# RPi.net
KiCad netlist of a schematic drawn in Altium Designer
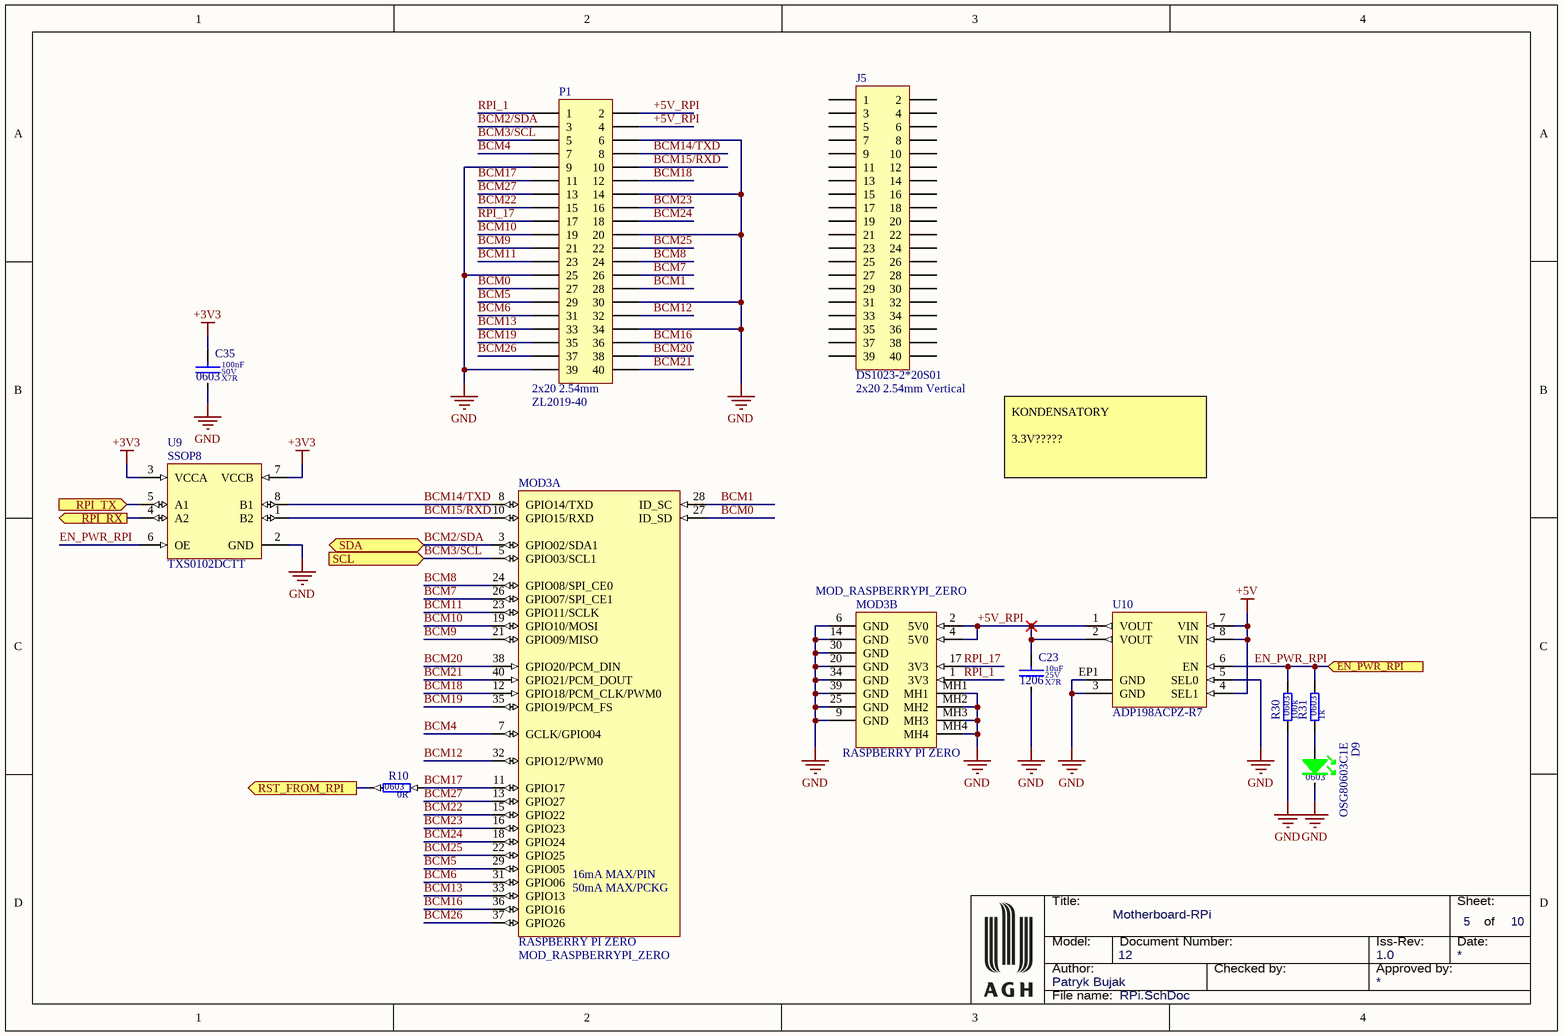
[diagram p0: RPi.SchDoc]

(export (version "E")
  (design (tool "Eeschema 10.0.6"))
  (components
    (comp (ref "C23")
      (value "10uF")
      (footprint "C_1206_3216")
      (description "Capacitor")
      (fields
        (field (name "DIELECTRIC") "X7R")
        (field (name "VOLTAGE") "25V")
        (field (name "SCH_FOOTPRINT") "1206")
        (field (name "PART NUMBER") "C_10uF_25V_X7R_1206_10")
        (field (name "MANUFACTURER") "Samsung Electro-Mechanics")
      )
      (libsource (lib "Library") (part "C"))
    )
    (comp (ref "C35")
      (value "100nF")
      (footprint "C_0603_1608")
      (description "Capacitor")
      (fields
        (field (name "DIELECTRIC") "X7R")
        (field (name "VOLTAGE") "50V")
        (field (name "SCH_FOOTPRINT") "0603")
        (field (name "PART NUMBER") "C_100nF_50V_X7R_0603_5")
        (field (name "MANUFACTURER") "Samsung")
      )
      (libsource (lib "Library") (part "C"))
    )
    (comp (ref "D9")
      (value "OSG80603C1E")
      (footprint "OL_0603_1608")
      (description "LED GREEN")
      (fields
        (field (name "SCH_FOOTPRINT") "0603")
        (field (name "PART NUMBER") "OL_G_0603_OSG80603C1E")
        (field (name "MANUFACTURER") "Optosupply")
      )
      (libsource (lib "Library") (part "OL_G"))
    )
    (comp (ref "J5")
      (value "DS1023-2*20S01")
      (footprint "J_HEADER_2x20_2.54_VERTICAL")
      (description "Header, 40-Pin, Dual row")
      (fields
        (field (name "PART NUMBER") "J_HEADER_2x20_2.54_VERTICAL")
        (field (name "SCH_FOOTPRINT") "2x20 2.54mm Vertical")
        (field (name "MANUFACTURER") "Connfly")
      )
      (libsource (lib "Library") (part "J_HEADER_2x20"))
    )
    (comp (ref "MOD3")
      (value "RASPBERRY PI ZERO")
      (footprint "MOD_RASPBERRYPI_ZERO")
      (fields
        (field (name "PART NUMBER") "MOD_RASPBERRYPI_ZERO")
        (field (name "SCH_FOOTPRINT") "MOD_RASPBERRYPI_ZERO")
        (field (name "MANUFACTURER") "Raspberry Pi")
      )
      (libsource (lib "Library") (part "MOD_RASPBERRYPI_3B"))
    )
    (comp (ref "P1")
      (value "ZL2019-40")
      (footprint "P_HEADER_2x20_2.54_HIGH")
      (description "Header, 19-Pin, Dual row")
      (fields
        (field (name "SCH_FOOTPRINT") "2x20 2.54mm")
        (field (name "PART NUMBER") "P_HEADER_2x20_2.54_HIGH")
        (field (name "MANUFACTURER") "Ninigi")
      )
      (libsource (lib "Library") (part "P_HEADER_2x20"))
    )
    (comp (ref "R10")
      (value "0R")
      (footprint "R_0603_1608")
      (fields
        (field (name "SCH_FOOTPRINT") "0603")
        (field (name "PART NUMBER") "R_0R_0603_5")
        (field (name "VOLTAGE") "50V")
        (field (name "POWER") "100mW")
      )
      (libsource (lib "") (part "R_1"))
    )
    (comp (ref "R30")
      (value "100k")
      (footprint "R_0603_1608")
      (fields
        (field (name "SCH_FOOTPRINT") "0603")
        (field (name "PART NUMBER") "R_100k_0603_1")
        (field (name "VOLTAGE") "50V")
        (field (name "POWER") "100mW")
      )
      (libsource (lib "Library") (part "R"))
    )
    (comp (ref "R31")
      (value "1k")
      (footprint "R_0603_1608")
      (fields
        (field (name "SCH_FOOTPRINT") "0603")
        (field (name "PART NUMBER") "R_1k_0603_1")
        (field (name "VOLTAGE") "75V")
        (field (name "POWER") "100mW")
      )
      (libsource (lib "Library") (part "R"))
    )
    (comp (ref "U9")
      (value "TXS0102DCTT")
      (footprint "SSOP8_3x3")
      (fields
        (field (name "SCH_FOOTPRINT") "SSOP8")
        (field (name "PART NUMBER") "U_TXS0102DCTT")
        (field (name "MANUFACTURER") "Texas Instruments")
      )
      (libsource (lib "Library") (part "U_TXS0102_DCT_DCU"))
    )
    (comp (ref "U10")
      (value "ADP198ACPZ-R7")
      (footprint "LFCSP-8-10")
      (fields
        (field (name "SCH_FOOTPRINT") "LFCSP8")
        (field (name "PART NUMBER") "U_ADP198ACPZ-R7")
        (field (name "MANUFACTURER") "Analog Devices")
        (field (name "Comment") "high-side load switch")
      )
      (libsource (lib "Library") (part "U_ADP198ACPZ-R7"))
    )
  )
  (nets
    (net (code "1") (name "+3V3") (class "Default")
      (node (ref "C35") (pin "1") (pinfunction "1_1") (pintype "passive"))
      (node (ref "U9") (pin "3") (pinfunction "VCCA_3") (pintype "input"))
      (node (ref "U9") (pin "7") (pinfunction "VCCB_7") (pintype "input"))
    )
    (net (code "2") (name "+5V") (class "Default")
      (node (ref "U10") (pin "4") (pinfunction "SEL1_4") (pintype "input"))
      (node (ref "U10") (pin "7") (pinfunction "VIN_7") (pintype "input"))
      (node (ref "U10") (pin "8") (pinfunction "VIN_8") (pintype "input"))
    )
    (net (code "3") (name "/+5V_RPI") (class "Default")
      (node (ref "C23") (pin "1") (pinfunction "1_1") (pintype "passive"))
      (node (ref "MOD3") (pin "2") (pinfunction "5V0_2") (pintype "input"))
      (node (ref "MOD3") (pin "4") (pinfunction "5V0_4") (pintype "input"))
      (node (ref "P1") (pin "2") (pinfunction "2_2") (pintype "passive"))
      (node (ref "P1") (pin "4") (pinfunction "4_4") (pintype "passive"))
      (node (ref "U10") (pin "1") (pinfunction "VOUT_1") (pintype "output"))
      (node (ref "U10") (pin "2") (pinfunction "VOUT_2") (pintype "output"))
    )
    (net (code "4") (name "/BCM0") (class "Default")
      (node (ref "MOD3") (pin "27") (pinfunction "ID_SD_27") (pintype "input"))
      (node (ref "P1") (pin "27") (pinfunction "27_27") (pintype "passive"))
    )
    (net (code "5") (name "/BCM1") (class "Default")
      (node (ref "MOD3") (pin "28") (pinfunction "ID_SC_28") (pintype "input"))
      (node (ref "P1") (pin "28") (pinfunction "28_28") (pintype "passive"))
    )
    (net (code "6") (name "/BCM2{slash}SDA") (class "Default")
      (node (ref "MOD3") (pin "3") (pinfunction "GPIO02/SDA1_3") (pintype "bidirectional"))
      (node (ref "P1") (pin "3") (pinfunction "3_3") (pintype "passive"))
    )
    (net (code "7") (name "/BCM3{slash}SCL") (class "Default")
      (node (ref "MOD3") (pin "5") (pinfunction "GPIO03/SCL1_5") (pintype "bidirectional"))
      (node (ref "P1") (pin "5") (pinfunction "5_5") (pintype "passive"))
    )
    (net (code "8") (name "/BCM4") (class "Default")
      (node (ref "MOD3") (pin "7") (pinfunction "GCLK/GPIO04_7") (pintype "bidirectional"))
      (node (ref "P1") (pin "7") (pinfunction "7_7") (pintype "passive"))
    )
    (net (code "9") (name "/BCM5") (class "Default")
      (node (ref "MOD3") (pin "29") (pinfunction "GPIO05_29") (pintype "bidirectional"))
      (node (ref "P1") (pin "29") (pinfunction "29_29") (pintype "passive"))
    )
    (net (code "10") (name "/BCM6") (class "Default")
      (node (ref "MOD3") (pin "31") (pinfunction "GPIO06_31") (pintype "bidirectional"))
      (node (ref "P1") (pin "31") (pinfunction "31_31") (pintype "passive"))
    )
    (net (code "11") (name "/BCM7") (class "Default")
      (node (ref "MOD3") (pin "26") (pinfunction "GPIO07/SPI_CE1_26") (pintype "bidirectional"))
      (node (ref "P1") (pin "26") (pinfunction "26_26") (pintype "passive"))
    )
    (net (code "12") (name "/BCM8") (class "Default")
      (node (ref "MOD3") (pin "24") (pinfunction "GPIO08/SPI_CE0_24") (pintype "bidirectional"))
      (node (ref "P1") (pin "24") (pinfunction "24_24") (pintype "passive"))
    )
    (net (code "13") (name "/BCM9") (class "Default")
      (node (ref "MOD3") (pin "21") (pinfunction "GPIO09/MISO_21") (pintype "bidirectional"))
      (node (ref "P1") (pin "21") (pinfunction "21_21") (pintype "passive"))
    )
    (net (code "14") (name "/BCM10") (class "Default")
      (node (ref "MOD3") (pin "19") (pinfunction "GPIO10/MOSI_19") (pintype "bidirectional"))
      (node (ref "P1") (pin "19") (pinfunction "19_19") (pintype "passive"))
    )
    (net (code "15") (name "/BCM11") (class "Default")
      (node (ref "MOD3") (pin "23") (pinfunction "GPIO11/SCLK_23") (pintype "bidirectional"))
      (node (ref "P1") (pin "23") (pinfunction "23_23") (pintype "passive"))
    )
    (net (code "16") (name "/BCM12") (class "Default")
      (node (ref "MOD3") (pin "32") (pinfunction "GPIO12/PWM0_32") (pintype "bidirectional"))
      (node (ref "P1") (pin "32") (pinfunction "32_32") (pintype "passive"))
    )
    (net (code "17") (name "/BCM13") (class "Default")
      (node (ref "MOD3") (pin "33") (pinfunction "GPIO13_33") (pintype "bidirectional"))
      (node (ref "P1") (pin "33") (pinfunction "33_33") (pintype "passive"))
    )
    (net (code "18") (name "/BCM14{slash}TXD") (class "Default")
      (node (ref "MOD3") (pin "8") (pinfunction "GPIO14/TXD_8") (pintype "bidirectional"))
      (node (ref "P1") (pin "8") (pinfunction "8_8") (pintype "passive"))
      (node (ref "U9") (pin "8") (pinfunction "B1_8") (pintype "bidirectional"))
    )
    (net (code "19") (name "/BCM15{slash}RXD") (class "Default")
      (node (ref "MOD3") (pin "10") (pinfunction "GPIO15/RXD_10") (pintype "bidirectional"))
      (node (ref "P1") (pin "10") (pinfunction "10_10") (pintype "passive"))
      (node (ref "U9") (pin "1") (pinfunction "B2_1") (pintype "bidirectional"))
    )
    (net (code "20") (name "/BCM16") (class "Default")
      (node (ref "MOD3") (pin "36") (pinfunction "GPIO16_36") (pintype "bidirectional"))
      (node (ref "P1") (pin "36") (pinfunction "36_36") (pintype "passive"))
    )
    (net (code "21") (name "/BCM17") (class "Default")
      (node (ref "MOD3") (pin "11") (pinfunction "GPIO17_11") (pintype "bidirectional"))
      (node (ref "P1") (pin "11") (pinfunction "11_11") (pintype "passive"))
      (node (ref "R10") (pin "1") (pinfunction "1_1") (pintype "input"))
    )
    (net (code "22") (name "/BCM18") (class "Default")
      (node (ref "MOD3") (pin "12") (pinfunction "GPIO18/PCM_CLK/PWM0_12") (pintype "input"))
      (node (ref "P1") (pin "12") (pinfunction "12_12") (pintype "passive"))
    )
    (net (code "23") (name "/BCM19") (class "Default")
      (node (ref "MOD3") (pin "35") (pinfunction "GPIO19/PCM_FS_35") (pintype "bidirectional"))
      (node (ref "P1") (pin "35") (pinfunction "35_35") (pintype "passive"))
    )
    (net (code "24") (name "/BCM20") (class "Default")
      (node (ref "MOD3") (pin "38") (pinfunction "GPIO20/PCM_DIN_38") (pintype "input"))
      (node (ref "P1") (pin "38") (pinfunction "38_38") (pintype "passive"))
    )
    (net (code "25") (name "/BCM21") (class "Default")
      (node (ref "MOD3") (pin "40") (pinfunction "GPIO21/PCM_DOUT_40") (pintype "input"))
      (node (ref "P1") (pin "40") (pinfunction "40_40") (pintype "passive"))
    )
    (net (code "26") (name "/BCM22") (class "Default")
      (node (ref "MOD3") (pin "15") (pinfunction "GPIO22_15") (pintype "bidirectional"))
      (node (ref "P1") (pin "15") (pinfunction "15_15") (pintype "passive"))
    )
    (net (code "27") (name "/BCM23") (class "Default")
      (node (ref "MOD3") (pin "16") (pinfunction "GPIO23_16") (pintype "bidirectional"))
      (node (ref "P1") (pin "16") (pinfunction "16_16") (pintype "passive"))
    )
    (net (code "28") (name "/BCM24") (class "Default")
      (node (ref "MOD3") (pin "18") (pinfunction "GPIO24_18") (pintype "bidirectional"))
      (node (ref "P1") (pin "18") (pinfunction "18_18") (pintype "passive"))
    )
    (net (code "29") (name "/BCM25") (class "Default")
      (node (ref "MOD3") (pin "22") (pinfunction "GPIO25_22") (pintype "bidirectional"))
      (node (ref "P1") (pin "22") (pinfunction "22_22") (pintype "passive"))
    )
    (net (code "30") (name "/BCM26") (class "Default")
      (node (ref "MOD3") (pin "37") (pinfunction "GPIO26_37") (pintype "bidirectional"))
      (node (ref "P1") (pin "37") (pinfunction "37_37") (pintype "passive"))
    )
    (net (code "31") (name "/BCM27") (class "Default")
      (node (ref "MOD3") (pin "13") (pinfunction "GPIO27_13") (pintype "bidirectional"))
      (node (ref "P1") (pin "13") (pinfunction "13_13") (pintype "passive"))
    )
    (net (code "32") (name "/EN_PWR_RPI") (class "Default")
      (node (ref "R30") (pin "2") (pinfunction "2_2") (pintype "passive"))
      (node (ref "R31") (pin "2") (pinfunction "2_2") (pintype "passive"))
      (node (ref "U10") (pin "6") (pinfunction "EN_6") (pintype "input"))
      (node (ref "U9") (pin "6") (pinfunction "OE_6") (pintype "input"))
    )
    (net (code "33") (name "/RPI_1") (class "Default")
      (node (ref "MOD3") (pin "1") (pinfunction "3V3_1") (pintype "input"))
      (node (ref "P1") (pin "1") (pinfunction "1_1") (pintype "passive"))
    )
    (net (code "34") (name "/RPI_17") (class "Default")
      (node (ref "MOD3") (pin "17") (pinfunction "3V3_17") (pintype "input"))
      (node (ref "P1") (pin "17") (pinfunction "17_17") (pintype "passive"))
    )
    (net (code "35") (name "/RPI_RX") (class "Default")
      (node (ref "U9") (pin "4") (pinfunction "A2_4") (pintype "bidirectional"))
    )
    (net (code "36") (name "/RPI_TX") (class "Default")
      (node (ref "U9") (pin "5") (pinfunction "A1_5") (pintype "bidirectional"))
    )
    (net (code "37") (name "/RST_FROM_RPI") (class "Default")
      (node (ref "R10") (pin "2") (pinfunction "2_2") (pintype "output"))
    )
    (net (code "38") (name "GND") (class "Default")
      (node (ref "C23") (pin "2") (pinfunction "2_2") (pintype "passive"))
      (node (ref "C35") (pin "2") (pinfunction "2_2") (pintype "passive"))
      (node (ref "D9") (pin "1") (pinfunction "K_1") (pintype "passive"))
      (node (ref "MOD3") (pin "14") (pinfunction "GND_14") (pintype "power_in"))
      (node (ref "MOD3") (pin "20") (pinfunction "GND_20") (pintype "power_in"))
      (node (ref "MOD3") (pin "25") (pinfunction "GND_25") (pintype "power_in"))
      (node (ref "MOD3") (pin "30") (pinfunction "GND_30") (pintype "power_in"))
      (node (ref "MOD3") (pin "34") (pinfunction "GND_34") (pintype "power_in"))
      (node (ref "MOD3") (pin "39") (pinfunction "GND_39") (pintype "power_in"))
      (node (ref "MOD3") (pin "6") (pinfunction "GND_6") (pintype "power_in"))
      (node (ref "MOD3") (pin "9") (pinfunction "GND_9") (pintype "power_in"))
      (node (ref "MOD3") (pin "MH1") (pinfunction "MH1_MH1") (pintype "passive"))
      (node (ref "MOD3") (pin "MH2") (pinfunction "MH2_MH2") (pintype "passive"))
      (node (ref "MOD3") (pin "MH3") (pinfunction "MH3_MH3") (pintype "passive"))
      (node (ref "MOD3") (pin "MH4") (pinfunction "MH4_MH4") (pintype "passive"))
      (node (ref "P1") (pin "14") (pinfunction "14_14") (pintype "passive"))
      (node (ref "P1") (pin "20") (pinfunction "20_20") (pintype "passive"))
      (node (ref "P1") (pin "25") (pinfunction "25_25") (pintype "passive"))
      (node (ref "P1") (pin "30") (pinfunction "30_30") (pintype "passive"))
      (node (ref "P1") (pin "34") (pinfunction "34_34") (pintype "passive"))
      (node (ref "P1") (pin "39") (pinfunction "39_39") (pintype "passive"))
      (node (ref "P1") (pin "6") (pinfunction "6_6") (pintype "passive"))
      (node (ref "P1") (pin "9") (pinfunction "9_9") (pintype "passive"))
      (node (ref "R30") (pin "1") (pinfunction "1_1") (pintype "passive"))
      (node (ref "U10") (pin "3") (pinfunction "GND_3") (pintype "power_in"))
      (node (ref "U10") (pin "5") (pinfunction "SEL0_5") (pintype "input"))
      (node (ref "U10") (pin "EP1") (pinfunction "GND_EP1") (pintype "power_in"))
      (node (ref "U9") (pin "2") (pinfunction "GND_2") (pintype "power_in"))
    )
    (net (code "39") (name "Net-(D9-A)") (class "Default")
      (node (ref "D9") (pin "2") (pinfunction "A_2") (pintype "passive"))
      (node (ref "R31") (pin "1") (pinfunction "1_1") (pintype "passive"))
    )
    (net (code "40") (name "unconnected-(J5-Pad1)") (class "Default")
      (node (ref "J5") (pin "1") (pinfunction "1_1") (pintype "passive"))
    )
    (net (code "41") (name "unconnected-(J5-Pad2)") (class "Default")
      (node (ref "J5") (pin "2") (pinfunction "2_2") (pintype "passive"))
    )
    (net (code "42") (name "unconnected-(J5-Pad3)") (class "Default")
      (node (ref "J5") (pin "3") (pinfunction "3_3") (pintype "passive"))
    )
    (net (code "43") (name "unconnected-(J5-Pad4)") (class "Default")
      (node (ref "J5") (pin "4") (pinfunction "4_4") (pintype "passive"))
    )
    (net (code "44") (name "unconnected-(J5-Pad5)") (class "Default")
      (node (ref "J5") (pin "5") (pinfunction "5_5") (pintype "passive"))
    )
    (net (code "45") (name "unconnected-(J5-Pad6)") (class "Default")
      (node (ref "J5") (pin "6") (pinfunction "6_6") (pintype "passive"))
    )
    (net (code "46") (name "unconnected-(J5-Pad7)") (class "Default")
      (node (ref "J5") (pin "7") (pinfunction "7_7") (pintype "passive"))
    )
    (net (code "47") (name "unconnected-(J5-Pad8)") (class "Default")
      (node (ref "J5") (pin "8") (pinfunction "8_8") (pintype "passive"))
    )
    (net (code "48") (name "unconnected-(J5-Pad9)") (class "Default")
      (node (ref "J5") (pin "9") (pinfunction "9_9") (pintype "passive"))
    )
    (net (code "49") (name "unconnected-(J5-Pad10)") (class "Default")
      (node (ref "J5") (pin "10") (pinfunction "10_10") (pintype "passive"))
    )
    (net (code "50") (name "unconnected-(J5-Pad11)") (class "Default")
      (node (ref "J5") (pin "11") (pinfunction "11_11") (pintype "passive"))
    )
    (net (code "51") (name "unconnected-(J5-Pad12)") (class "Default")
      (node (ref "J5") (pin "12") (pinfunction "12_12") (pintype "passive"))
    )
    (net (code "52") (name "unconnected-(J5-Pad13)") (class "Default")
      (node (ref "J5") (pin "13") (pinfunction "13_13") (pintype "passive"))
    )
    (net (code "53") (name "unconnected-(J5-Pad14)") (class "Default")
      (node (ref "J5") (pin "14") (pinfunction "14_14") (pintype "passive"))
    )
    (net (code "54") (name "unconnected-(J5-Pad15)") (class "Default")
      (node (ref "J5") (pin "15") (pinfunction "15_15") (pintype "passive"))
    )
    (net (code "55") (name "unconnected-(J5-Pad16)") (class "Default")
      (node (ref "J5") (pin "16") (pinfunction "16_16") (pintype "passive"))
    )
    (net (code "56") (name "unconnected-(J5-Pad17)") (class "Default")
      (node (ref "J5") (pin "17") (pinfunction "17_17") (pintype "passive"))
    )
    (net (code "57") (name "unconnected-(J5-Pad18)") (class "Default")
      (node (ref "J5") (pin "18") (pinfunction "18_18") (pintype "passive"))
    )
    (net (code "58") (name "unconnected-(J5-Pad19)") (class "Default")
      (node (ref "J5") (pin "19") (pinfunction "19_19") (pintype "passive"))
    )
    (net (code "59") (name "unconnected-(J5-Pad20)") (class "Default")
      (node (ref "J5") (pin "20") (pinfunction "20_20") (pintype "passive"))
    )
    (net (code "60") (name "unconnected-(J5-Pad21)") (class "Default")
      (node (ref "J5") (pin "21") (pinfunction "21_21") (pintype "passive"))
    )
    (net (code "61") (name "unconnected-(J5-Pad22)") (class "Default")
      (node (ref "J5") (pin "22") (pinfunction "22_22") (pintype "passive"))
    )
    (net (code "62") (name "unconnected-(J5-Pad23)") (class "Default")
      (node (ref "J5") (pin "23") (pinfunction "23_23") (pintype "passive"))
    )
    (net (code "63") (name "unconnected-(J5-Pad24)") (class "Default")
      (node (ref "J5") (pin "24") (pinfunction "24_24") (pintype "passive"))
    )
    (net (code "64") (name "unconnected-(J5-Pad25)") (class "Default")
      (node (ref "J5") (pin "25") (pinfunction "25_25") (pintype "passive"))
    )
    (net (code "65") (name "unconnected-(J5-Pad26)") (class "Default")
      (node (ref "J5") (pin "26") (pinfunction "26_26") (pintype "passive"))
    )
    (net (code "66") (name "unconnected-(J5-Pad27)") (class "Default")
      (node (ref "J5") (pin "27") (pinfunction "27_27") (pintype "passive"))
    )
    (net (code "67") (name "unconnected-(J5-Pad28)") (class "Default")
      (node (ref "J5") (pin "28") (pinfunction "28_28") (pintype "passive"))
    )
    (net (code "68") (name "unconnected-(J5-Pad29)") (class "Default")
      (node (ref "J5") (pin "29") (pinfunction "29_29") (pintype "passive"))
    )
    (net (code "69") (name "unconnected-(J5-Pad30)") (class "Default")
      (node (ref "J5") (pin "30") (pinfunction "30_30") (pintype "passive"))
    )
    (net (code "70") (name "unconnected-(J5-Pad31)") (class "Default")
      (node (ref "J5") (pin "31") (pinfunction "31_31") (pintype "passive"))
    )
    (net (code "71") (name "unconnected-(J5-Pad32)") (class "Default")
      (node (ref "J5") (pin "32") (pinfunction "32_32") (pintype "passive"))
    )
    (net (code "72") (name "unconnected-(J5-Pad33)") (class "Default")
      (node (ref "J5") (pin "33") (pinfunction "33_33") (pintype "passive"))
    )
    (net (code "73") (name "unconnected-(J5-Pad34)") (class "Default")
      (node (ref "J5") (pin "34") (pinfunction "34_34") (pintype "passive"))
    )
    (net (code "74") (name "unconnected-(J5-Pad35)") (class "Default")
      (node (ref "J5") (pin "35") (pinfunction "35_35") (pintype "passive"))
    )
    (net (code "75") (name "unconnected-(J5-Pad36)") (class "Default")
      (node (ref "J5") (pin "36") (pinfunction "36_36") (pintype "passive"))
    )
    (net (code "76") (name "unconnected-(J5-Pad37)") (class "Default")
      (node (ref "J5") (pin "37") (pinfunction "37_37") (pintype "passive"))
    )
    (net (code "77") (name "unconnected-(J5-Pad38)") (class "Default")
      (node (ref "J5") (pin "38") (pinfunction "38_38") (pintype "passive"))
    )
    (net (code "78") (name "unconnected-(J5-Pad39)") (class "Default")
      (node (ref "J5") (pin "39") (pinfunction "39_39") (pintype "passive"))
    )
    (net (code "79") (name "unconnected-(J5-Pad40)") (class "Default")
      (node (ref "J5") (pin "40") (pinfunction "40_40") (pintype "passive"))
    )
  )
)
